# QCopterMV_KEY_Sch.net
KiCad netlist of a schematic drawn in Altium Designer
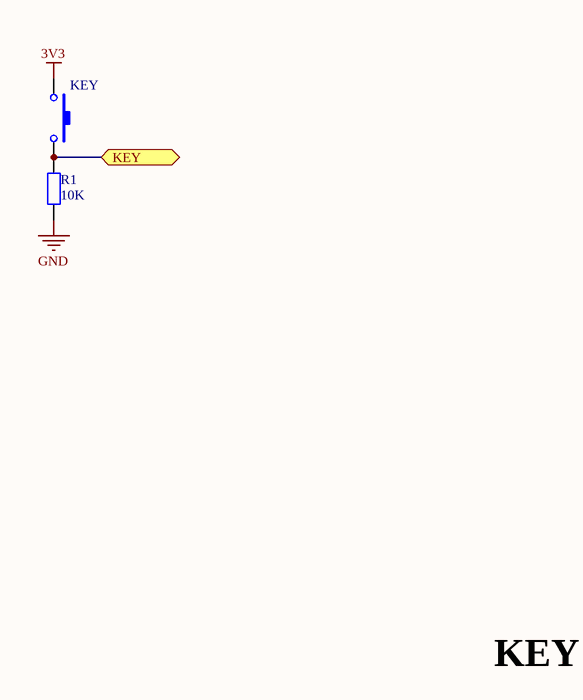
[diagram p0: QCopterMV_KEY_Sch.SchDoc]

(export (version "E")
  (design (tool "Eeschema 10.0.6"))
  (components
    (comp (ref "KEY")
      (value "SW-PB_1")
      (footprint "PCB_Switch:BT_90_T")
      (description "Switch")
      (fields (field (name "PUBLISHER") "Altium Limited"))
      (libsource (lib "SCH_Switch") (part "SW-PB_1"))
    )
    (comp (ref "R1")
      (value "10K")
      (footprint "PCB_Passive:RES_0603")
      (description "Resistor")
      (fields (field (name "Comment") "Res_0603"))
      (libsource (lib "SCH_Passive") (part "Res_0603"))
    )
  )
  (nets
    (net (code "1") (name "/KEY") (class "Default")
      (node (ref "KEY") (pin "2") (pinfunction "2_2") (pintype "passive"))
      (node (ref "R1") (pin "2") (pinfunction "2_2") (pintype "passive"))
    )
    (net (code "2") (name "3V3") (class "Default")
      (node (ref "KEY") (pin "1") (pinfunction "1_1") (pintype "passive"))
    )
    (net (code "3") (name "GND") (class "Default")
      (node (ref "R1") (pin "1") (pinfunction "1_1") (pintype "passive"))
    )
  )
)
